# Humidity.net
KiCad netlist of a schematic drawn in Altium Designer
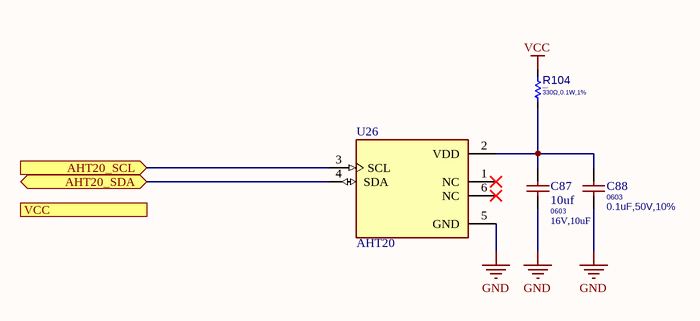
[diagram p0: Humidity.SchDoc]

(export (version "E")
  (design (tool "Eeschema 10.0.6"))
  (components
    (comp (ref "C87")
      (value "10uf")
      (footprint "CAPC1608X90N")
      (description "16V 10uF Y5V ±20% 0603 Multilayer Ceramic Capacitors MLCC - SMD/SMT ROHS")
      (fields
        (field (name "MANUFACTURER") "KEMET")
        (field (name "MPN") "CC0603KRX7R9BB104")
        (field (name "PACKAGE") "0603")
        (field (name "ALTIUM_VALUE") "16V,10uF")
      )
      (libsource (lib "RCL") (part "0603F106M160NT"))
    )
    (comp (ref "C88")
      (value "0.1uF,50V,10%")
      (footprint "C0603")
      (description "CAP CER 0.1UF 50V X7R 0603")
      (fields
        (field (name "MANUFACTURER") "Murata Electronics")
        (field (name "MPN") "GCM188R71H104KA57J")
        (field (name "PACKAGE") "0603")
      )
      (libsource (lib "RCL") (part "GCM188R71H104KA57J"))
    )
    (comp (ref "R104")
      (value "330Ω,0.1W,1%")
      (footprint "R0603")
      (description "330 Ohms ±1% 0.1W, 1/10W Chip Resistor 0603 (1608 Metric) Moisture Resistant Thick Film")
      (fields
        (field (name "MPN") "RC0603FR-07330RL")
        (field (name "MANUFACTURER") "YAGEO")
        (field (name "PACKAGE") "0603")
      )
      (libsource (lib "RCL") (part "RC0603FR-07330RL"))
    )
    (comp (ref "U26")
      (value "AHT20")
      (footprint "IC:PSON100P300X300X110-6N")
      (description "Temperature and Humidity sensor")
      (fields (field (name "MF") "Asair"))
      (libsource (lib "IC") (part "AHT20"))
    )
  )
  (nets
    (net (code "1") (name "/AHT20_SCL") (class "Default")
      (node (ref "U26") (pin "3") (pinfunction "SCL_3") (pintype "input"))
    )
    (net (code "2") (name "/AHT20_SDA") (class "Default")
      (node (ref "U26") (pin "4") (pinfunction "SDA_4") (pintype "bidirectional"))
    )
    (net (code "3") (name "GND") (class "Default")
      (node (ref "C87") (pin "1") (pinfunction "1_1") (pintype "passive"))
      (node (ref "C88") (pin "1") (pinfunction "1_1") (pintype "passive"))
      (node (ref "U26") (pin "5") (pinfunction "GND_5") (pintype "power_in"))
    )
    (net (code "4") (name "Net-(U26-VDD)") (class "Default")
      (node (ref "C87") (pin "2") (pinfunction "2_2") (pintype "passive"))
      (node (ref "C88") (pin "2") (pinfunction "2_2") (pintype "passive"))
      (node (ref "R104") (pin "1") (pinfunction "1_1") (pintype "passive"))
      (node (ref "U26") (pin "2") (pinfunction "VDD_2") (pintype "power_in"))
    )
    (net (code "5") (name "VCC") (class "Default")
      (node (ref "R104") (pin "2") (pinfunction "2_2") (pintype "passive"))
    )
    (net (code "6") (name "unconnected-(U26-NC-Pad1)") (class "Default")
      (node (ref "U26") (pin "1") (pinfunction "NC_1") (pintype "passive+no_connect"))
    )
    (net (code "7") (name "unconnected-(U26-NC-Pad6)") (class "Default")
      (node (ref "U26") (pin "6") (pinfunction "NC_6") (pintype "passive+no_connect"))
    )
  )
)
